# USB-UART_PL2303_HX.net
KiCad netlist of a schematic drawn in Altium Designer
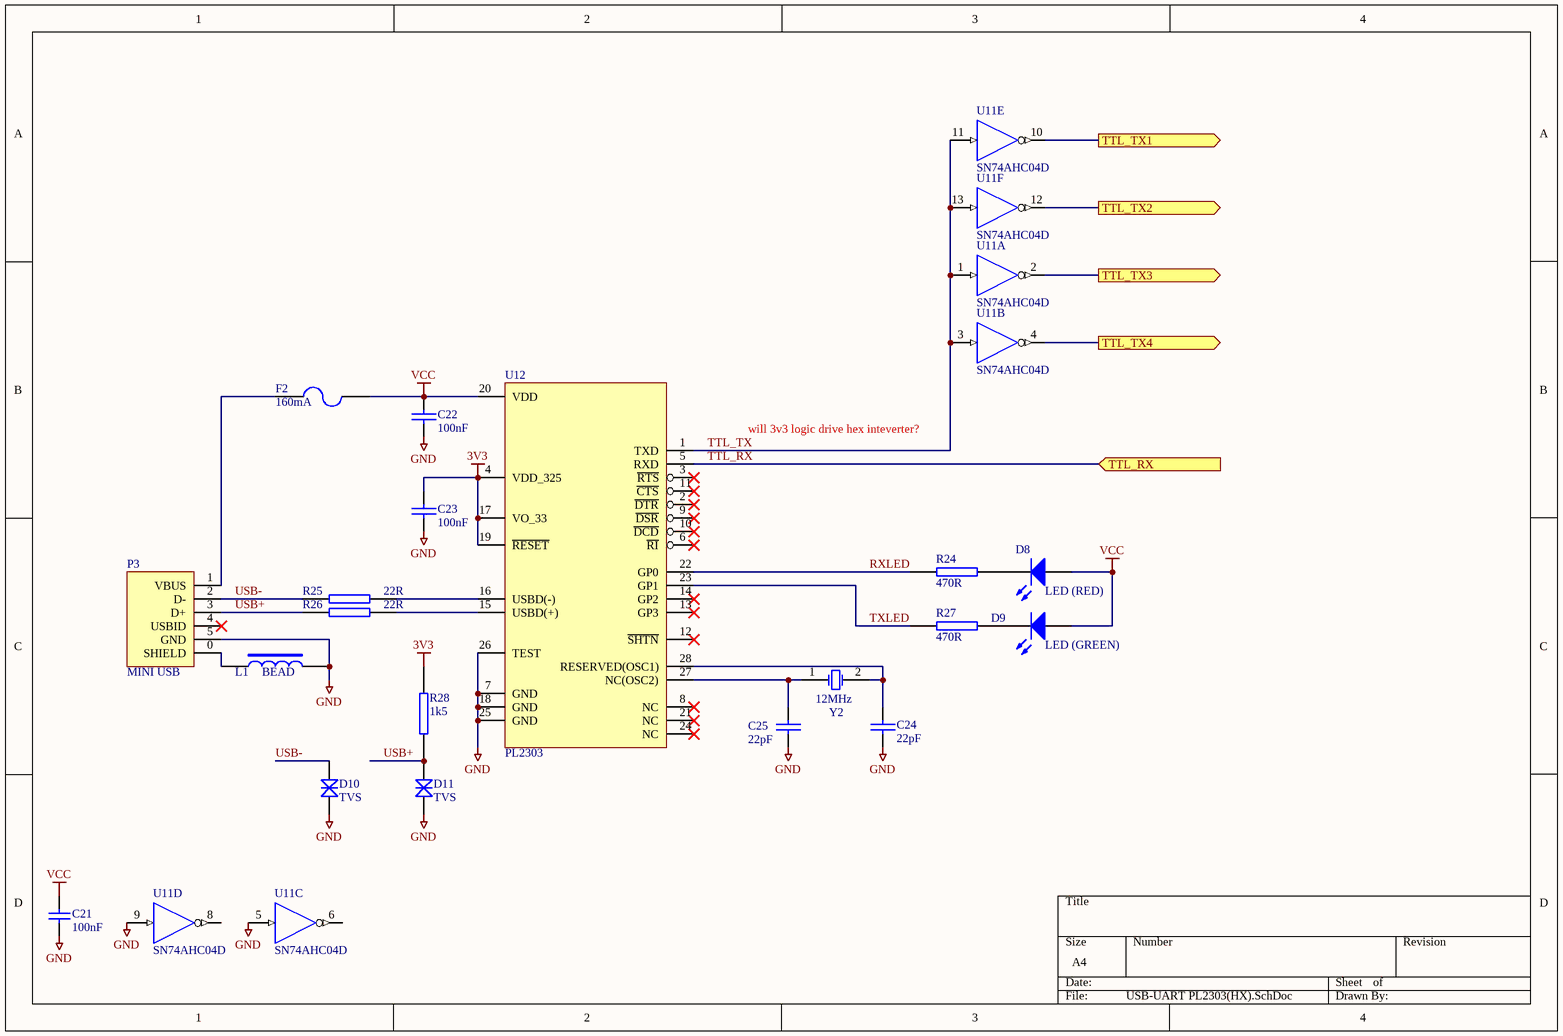
[diagram p0: USB-UART PL2303(HX).SchDoc]

(export (version "E")
  (design (tool "Eeschema 10.0.6"))
  (components
    (comp (ref "C21")
      (value "100nF")
      (footprint "CAP (3D) - 0603")
      (description "Capacitor")
      (libsource (lib "Miscellaneous Devices") (part "Cap"))
    )
    (comp (ref "C22")
      (value "100nF")
      (footprint "CAP (3D) - 0603")
      (description "CAPACITOR SMD 0603")
      (fields (field (name "MOUSER PART NO.") "81-GCM188R71C104KA7D") (field (name "MANUFACTURER") "Murata"))
      (libsource (lib "NASCO Capacitors") (part "CAP SMD 0603 100nF"))
    )
    (comp (ref "C23")
      (value "100nF")
      (footprint "CAP (3D) - 0603")
      (description "CAPACITOR SMD 0603")
      (fields (field (name "MOUSER PART NO.") "81-GCM188R71C104KA7D") (field (name "MANUFACTURER") "Murata"))
      (libsource (lib "NASCO Capacitors") (part "CAP SMD 0603 100nF"))
    )
    (comp (ref "C24")
      (value "22pF")
      (footprint "CAP (3D) - 0603")
      (description "CAPACITOR SMD 0603")
      (fields
        (field (name "MANUFACTURER") "Vishay")
        (field (name "MANUFACTURER PART NO.") "VJ0603A220JXACW1BC")
      )
      (libsource (lib "NASCO Capacitors") (part "CAP SMD 0603 1nF"))
    )
    (comp (ref "C25")
      (value "22pF")
      (footprint "CAP (3D) - 0603")
      (description "CAPACITOR SMD 0603")
      (fields
        (field (name "MANUFACTURER") "Vishay")
        (field (name "MANUFACTURER PART NO.") "VJ0603A220JXACW1BC")
      )
      (libsource (lib "NASCO Capacitors") (part "CAP SMD 0603 1nF"))
    )
    (comp (ref "D8")
      (value "LED (RED)")
      (footprint "LED(3D) 3MM VERTICAL (RED)")
      (description "3mm RED LED")
      (fields (field (name "MOUSER PART NO.") "859-LTL-4261NR") (field (name "MANUFACTURER") "Lite-On"))
      (libsource (lib "NASCO") (part "LED 3mm RED"))
    )
    (comp (ref "D9")
      (value "LED (GREEN)")
      (footprint "LED(3D) 3MM VERTICAL (GREEN)")
      (description "3mm GREEN LED")
      (fields (field (name "MOUSER PART NO.") "859-LTL-1CHG") (field (name "MANUFACTURER") "Lite-On"))
      (libsource (lib "NASCO") (part "LED 3mm GREEN"))
    )
    (comp (ref "D10")
      (value "TVS")
      (footprint "TVS (3D) - 0603")
      (description "Transient Voltage Suppression (TVS) Diode")
      (fields (field (name "MANUFACTURER PART NO.") "CG0603MLC-05E") (field (name "MANUFACTURER") "Bourns"))
      (libsource (lib "SIM900") (part "TVS DIODE"))
    )
    (comp (ref "D11")
      (value "TVS")
      (footprint "TVS (3D) - 0603")
      (description "Transient Voltage Suppression (TVS) Diode")
      (fields (field (name "MANUFACTURER PART NO.") "CG0603MLC-05E") (field (name "MANUFACTURER") "Bourns"))
      (libsource (lib "SIM900") (part "TVS DIODE"))
    )
    (comp (ref "F2")
      (value "160mA")
      (footprint "1206")
      (description "Fuse")
      (fields (field (name "MANUFACTURER") "Littlefuse") (field (name "MOUSER PART NO.") "576-1206L016WR"))
      (libsource (lib "Miscellaneous Devices") (part "Fuse 2"))
    )
    (comp (ref "L1")
      (value "BEAD")
      (footprint "RES (3D) - 1210")
      (description "INDUCTOR SMD 1210")
      (fields (field (name "MOUSER PART NO.") "636-2512063007Y3") (field (name "MANUFACTURER") "Fair-Rite"))
      (libsource (lib "NASCO") (part "INDUCTOR SMD 1210 100uH"))
    )
    (comp (ref "P3")
      (value "MINI USB")
      (footprint "MINI USB")
      (description "MICRO USB")
      (fields
        (field (name "MANUFACTURER") "Keystone Electronics")
        (field (name "MANUFACTURER PART NO.") "534-934")
      )
      (libsource (lib "SIM900") (part "MICRO USB"))
    )
    (comp (ref "R24")
      (value "470R")
      (footprint "RES (3D) - 0603")
      (description "RESISTOR SMD 0603 590R")
      (fields (field (name "MOUSER PART NO.") "71-CRCW0603J-470-E3") (field (name "MANUFACTURER") "Vishay"))
      (libsource (lib "NASCO Resistors") (part "RES SMD 0603 590R"))
    )
    (comp (ref "R25")
      (value "22R")
      (footprint "RES (3D) - 0603")
      (description "RESISTOR SMD 0603 0R")
      (fields (field (name "MANUFACTURER") "Xicon") (field (name "MANUFACTURER PART NO.") "301-22-RC"))
      (libsource (lib "NASCO Resistors") (part "RES SMD 0603 0R"))
    )
    (comp (ref "R26")
      (value "22R")
      (footprint "RES (3D) - 0603")
      (description "RESISTOR SMD 0603 0R")
      (fields (field (name "MANUFACTURER") "Xicon") (field (name "MANUFACTURER PART NO.") "301-22-RC"))
      (libsource (lib "NASCO Resistors") (part "RES SMD 0603 0R"))
    )
    (comp (ref "R27")
      (value "470R")
      (footprint "RES (3D) - 0603")
      (description "RESISTOR SMD 0603 590R")
      (fields (field (name "MOUSER PART NO.") "71-CRCW0603J-470-E3") (field (name "MANUFACTURER") "Vishay"))
      (libsource (lib "NASCO Resistors") (part "RES SMD 0603 590R"))
    )
    (comp (ref "R28")
      (value "1k5")
      (footprint "RES (3D) - 0603")
      (description "RESISTOR SMD 0603 0R")
      (libsource (lib "NASCO Resistors") (part "RES SMD 0603 0R"))
    )
    (comp (ref "U11")
      (value "SN74AHC04D")
      (footprint "SOIC-14")
      (description "Hex Inverter")
      (fields (field (name "PUBLISHER") "Altium Limited"))
      (libsource (lib "TI Logic Gate 1") (part "SN74AHC04D"))
    )
    (comp (ref "U12")
      (value "PL2303")
      (footprint "SSOP28")
      (description "PL2303 USB to 232 Converter (FT232 Compatible)")
      (libsource (lib "NASCO") (part "PL2303"))
    )
    (comp (ref "Y2")
      (value "12MHz")
      (footprint "CRYSTAL 3x8")
      (description "Crystal Oscillator")
      (fields (field (name "Comment") "XTAL"))
      (libsource (lib "Miscellaneous Devices") (part "XTAL"))
    )
  )
  (nets
    (net (code "1") (name "/RXLED") (class "Default")
      (node (ref "R24") (pin "1") (pinfunction "1_1") (pintype "passive"))
      (node (ref "U12") (pin "22") (pinfunction "GP0_22") (pintype "passive"))
    )
    (net (code "2") (name "/TTL_RX") (class "Default")
      (node (ref "U12") (pin "5") (pinfunction "RXD_5") (pintype "passive"))
    )
    (net (code "3") (name "/TTL_TX") (class "Default")
      (node (ref "U11") (pin "1") (pinfunction "A_1") (pintype "input"))
      (node (ref "U11") (pin "11") (pinfunction "A_11") (pintype "input"))
      (node (ref "U11") (pin "13") (pinfunction "A_13") (pintype "input"))
      (node (ref "U11") (pin "3") (pinfunction "A_3") (pintype "input"))
      (node (ref "U12") (pin "1") (pinfunction "TXD_1") (pintype "passive"))
    )
    (net (code "4") (name "/TTL_TX1") (class "Default")
      (node (ref "U11") (pin "10") (pinfunction "Y_10") (pintype "output"))
    )
    (net (code "5") (name "/TTL_TX2") (class "Default")
      (node (ref "U11") (pin "12") (pinfunction "Y_12") (pintype "output"))
    )
    (net (code "6") (name "/TTL_TX3") (class "Default")
      (node (ref "U11") (pin "2") (pinfunction "Y_2") (pintype "output"))
    )
    (net (code "7") (name "/TTL_TX4") (class "Default")
      (node (ref "U11") (pin "4") (pinfunction "Y_4") (pintype "output"))
    )
    (net (code "8") (name "/TXLED") (class "Default")
      (node (ref "R27") (pin "1") (pinfunction "1_1") (pintype "passive"))
      (node (ref "U12") (pin "23") (pinfunction "GP1_23") (pintype "passive"))
    )
    (net (code "9") (name "/USB+") (class "Default")
      (node (ref "D11") (pin "2") (pinfunction "K_2") (pintype "passive"))
      (node (ref "P3") (pin "3") (pinfunction "D+_3") (pintype "passive"))
      (node (ref "R26") (pin "1") (pinfunction "1_1") (pintype "passive"))
      (node (ref "R28") (pin "2") (pinfunction "2_2") (pintype "passive"))
    )
    (net (code "10") (name "/USB-") (class "Default")
      (node (ref "D10") (pin "2") (pinfunction "K_2") (pintype "passive"))
      (node (ref "P3") (pin "2") (pinfunction "D-_2") (pintype "passive"))
      (node (ref "R25") (pin "1") (pinfunction "1_1") (pintype "passive"))
    )
    (net (code "11") (name "3V3") (class "Default")
      (node (ref "C23") (pin "1") (pinfunction "1_1") (pintype "passive"))
      (node (ref "R28") (pin "1") (pinfunction "1_1") (pintype "passive"))
      (node (ref "U12") (pin "17") (pinfunction "VO_33_17") (pintype "passive"))
      (node (ref "U12") (pin "19") (pinfunction "~{RESET}_19") (pintype "passive"))
      (node (ref "U12") (pin "4") (pinfunction "VDD_325_4") (pintype "passive"))
    )
    (net (code "12") (name "GND") (class "Default")
      (node (ref "C21") (pin "1") (pinfunction "1_1") (pintype "passive"))
      (node (ref "C22") (pin "2") (pinfunction "2_2") (pintype "passive"))
      (node (ref "C23") (pin "2") (pinfunction "2_2") (pintype "passive"))
      (node (ref "C24") (pin "2") (pinfunction "2_2") (pintype "passive"))
      (node (ref "C25") (pin "2") (pinfunction "2_2") (pintype "passive"))
      (node (ref "D10") (pin "1") (pinfunction "A_1") (pintype "passive"))
      (node (ref "D11") (pin "1") (pinfunction "A_1") (pintype "passive"))
      (node (ref "L1") (pin "2") (pinfunction "2_2") (pintype "passive"))
      (node (ref "P3") (pin "5") (pinfunction "GND_5") (pintype "passive"))
      (node (ref "U11") (pin "5") (pinfunction "A_5") (pintype "input"))
      (node (ref "U11") (pin "7") (pinfunction "GND_7") (pintype "power_in"))
      (node (ref "U11") (pin "9") (pinfunction "A_9") (pintype "input"))
      (node (ref "U12") (pin "18") (pinfunction "GND_18") (pintype "passive"))
      (node (ref "U12") (pin "25") (pinfunction "GND_25") (pintype "passive"))
      (node (ref "U12") (pin "26") (pinfunction "TEST_26") (pintype "passive"))
      (node (ref "U12") (pin "7") (pinfunction "GND_7") (pintype "passive"))
    )
    (net (code "13") (name "Net-(D8-K)") (class "Default")
      (node (ref "D8") (pin "2") (pinfunction "K_2") (pintype "passive"))
      (node (ref "R24") (pin "2") (pinfunction "2_2") (pintype "passive"))
    )
    (net (code "14") (name "Net-(D9-K)") (class "Default")
      (node (ref "D9") (pin "2") (pinfunction "K_2") (pintype "passive"))
      (node (ref "R27") (pin "2") (pinfunction "2_2") (pintype "passive"))
    )
    (net (code "15") (name "Net-(P3-SHIELD)") (class "Default")
      (node (ref "L1") (pin "1") (pinfunction "1_1") (pintype "passive"))
      (node (ref "P3") (pin "0") (pinfunction "SHIELD_0") (pintype "passive"))
    )
    (net (code "16") (name "Net-(P3-VBUS)") (class "Default")
      (node (ref "F2") (pin "1") (pinfunction "1_1") (pintype "passive"))
      (node (ref "P3") (pin "1") (pinfunction "VBUS_1") (pintype "passive"))
    )
    (net (code "17") (name "Net-(U12-NC(OSC2))") (class "Default")
      (node (ref "C25") (pin "1") (pinfunction "1_1") (pintype "passive"))
      (node (ref "U12") (pin "27") (pinfunction "NC(OSC2)_27") (pintype "passive"))
      (node (ref "Y2") (pin "1") (pinfunction "OSC1_1") (pintype "passive"))
    )
    (net (code "18") (name "Net-(U12-RESERVED(OSC1))") (class "Default")
      (node (ref "C24") (pin "1") (pinfunction "1_1") (pintype "passive"))
      (node (ref "U12") (pin "28") (pinfunction "RESERVED(OSC1)_28") (pintype "passive"))
      (node (ref "Y2") (pin "2") (pinfunction "OSC2_2") (pintype "passive"))
    )
    (net (code "19") (name "Net-(U12-USBD(+))") (class "Default")
      (node (ref "R26") (pin "2") (pinfunction "2_2") (pintype "passive"))
      (node (ref "U12") (pin "15") (pinfunction "USBD(+)_15") (pintype "passive"))
    )
    (net (code "20") (name "Net-(U12-USBD(-))") (class "Default")
      (node (ref "R25") (pin "2") (pinfunction "2_2") (pintype "passive"))
      (node (ref "U12") (pin "16") (pinfunction "USBD(-)_16") (pintype "passive"))
    )
    (net (code "21") (name "VCC") (class "Default")
      (node (ref "C21") (pin "2") (pinfunction "2_2") (pintype "passive"))
      (node (ref "C22") (pin "1") (pinfunction "1_1") (pintype "passive"))
      (node (ref "D8") (pin "1") (pinfunction "A_1") (pintype "passive"))
      (node (ref "D9") (pin "1") (pinfunction "A_1") (pintype "passive"))
      (node (ref "F2") (pin "2") (pinfunction "2_2") (pintype "passive"))
      (node (ref "U11") (pin "14") (pinfunction "VCC_14") (pintype "power_in"))
      (node (ref "U12") (pin "20") (pinfunction "VDD_20") (pintype "passive"))
    )
    (net (code "22") (name "unconnected-(P3-USBID-Pad4)") (class "Default")
      (node (ref "P3") (pin "4") (pinfunction "USBID_4") (pintype "passive+no_connect"))
    )
    (net (code "23") (name "unconnected-(U11C-Y-Pad6)") (class "Default")
      (node (ref "U11") (pin "6") (pinfunction "Y_6") (pintype "output"))
    )
    (net (code "24") (name "unconnected-(U11D-Y-Pad8)") (class "Default")
      (node (ref "U11") (pin "8") (pinfunction "Y_8") (pintype "output"))
    )
    (net (code "25") (name "unconnected-(U12-GP2-Pad14)") (class "Default")
      (node (ref "U12") (pin "14") (pinfunction "GP2_14") (pintype "passive+no_connect"))
    )
    (net (code "26") (name "unconnected-(U12-GP3-Pad13)") (class "Default")
      (node (ref "U12") (pin "13") (pinfunction "GP3_13") (pintype "passive+no_connect"))
    )
    (net (code "27") (name "unconnected-(U12-NC-Pad8)") (class "Default")
      (node (ref "U12") (pin "8") (pinfunction "NC_8") (pintype "passive+no_connect"))
    )
    (net (code "28") (name "unconnected-(U12-NC-Pad21)") (class "Default")
      (node (ref "U12") (pin "21") (pinfunction "NC_21") (pintype "passive+no_connect"))
    )
    (net (code "29") (name "unconnected-(U12-NC-Pad24)") (class "Default")
      (node (ref "U12") (pin "24") (pinfunction "NC_24") (pintype "passive+no_connect"))
    )
    (net (code "30") (name "unconnected-(U12-~{CTS}-Pad11)") (class "Default")
      (node (ref "U12") (pin "11") (pinfunction "~{CTS}_11") (pintype "passive+no_connect"))
    )
    (net (code "31") (name "unconnected-(U12-~{DCD}-Pad10)") (class "Default")
      (node (ref "U12") (pin "10") (pinfunction "~{DCD}_10") (pintype "passive+no_connect"))
    )
    (net (code "32") (name "unconnected-(U12-~{DSR}-Pad9)") (class "Default")
      (node (ref "U12") (pin "9") (pinfunction "~{DSR}_9") (pintype "passive+no_connect"))
    )
    (net (code "33") (name "unconnected-(U12-~{DTR}-Pad2)") (class "Default")
      (node (ref "U12") (pin "2") (pinfunction "~{DTR}_2") (pintype "passive+no_connect"))
    )
    (net (code "34") (name "unconnected-(U12-~{RI}-Pad6)") (class "Default")
      (node (ref "U12") (pin "6") (pinfunction "~{RI}_6") (pintype "passive+no_connect"))
    )
    (net (code "35") (name "unconnected-(U12-~{RTS}-Pad3)") (class "Default")
      (node (ref "U12") (pin "3") (pinfunction "~{RTS}_3") (pintype "passive+no_connect"))
    )
    (net (code "36") (name "unconnected-(U12-~{SHTN}-Pad12)") (class "Default")
      (node (ref "U12") (pin "12") (pinfunction "~{SHTN}_12") (pintype "passive+no_connect"))
    )
  )
)
